# Motor_Driver_r1_1.net
KiCad netlist of a schematic drawn in Altium Designer
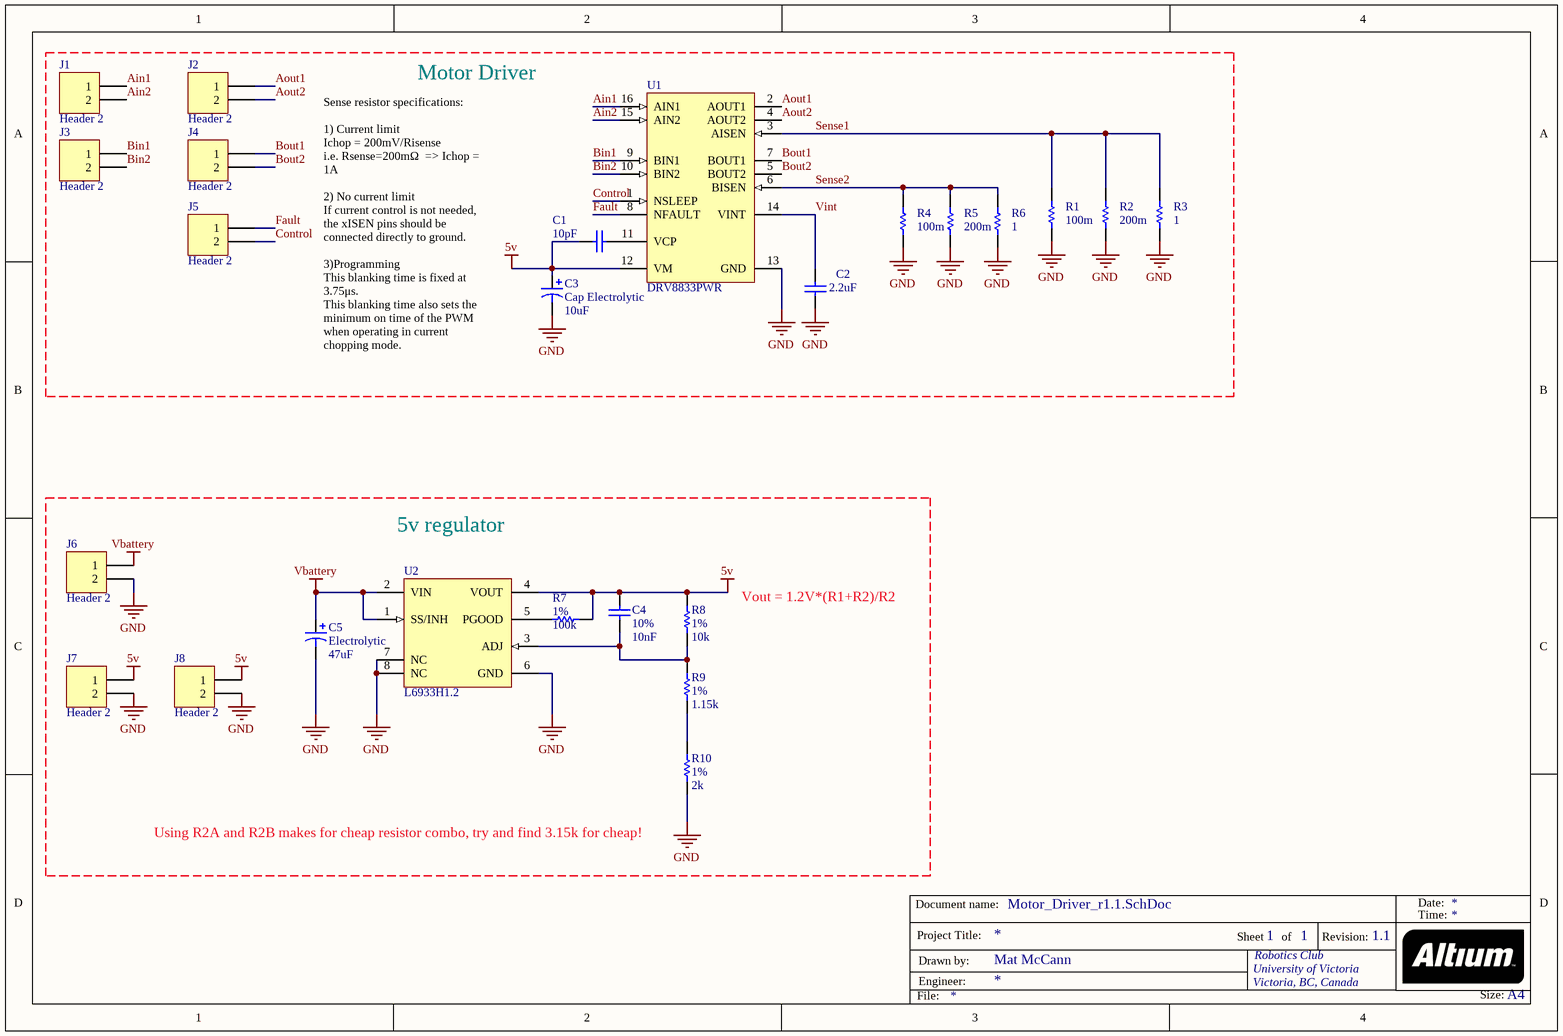
[diagram p0: Motor_Driver_r1.1.SchDoc]

(export (version "E")
  (design (tool "Eeschema 10.0.6"))
  (components
    (comp (ref "C1")
      (value "10pF")
      (footprint "6-0805_M")
      (description "Capacitor")
      (fields (field (name "Comment") "cap") (field (name "PUBLISHER") "Altium Limited"))
      (libsource (lib "Miscellaneous Devices") (part "Cap"))
    )
    (comp (ref "C2")
      (value "2.2uF")
      (footprint "6-0805_M")
      (description "Capacitor")
      (fields (field (name "Comment") "cap") (field (name "PUBLISHER") "Altium Limited"))
      (libsource (lib "Miscellaneous Devices") (part "Cap"))
    )
    (comp (ref "C3")
      (value "Cap Electrolytic")
      (footprint "capacitor_3d")
      (description "Polarized Capacitor (Radial)")
      (fields (field (name "ALTIUM_VALUE") "10uF") (field (name "PUBLISHER") "Altium Limited"))
      (libsource (lib "Miscellaneous Devices") (part "Cap Pol1"))
    )
    (comp (ref "C4")
      (value "10%")
      (footprint "6-0805_M")
      (description "Capacitor")
      (fields (field (name "ALTIUM_VALUE") "10nF") (field (name "PUBLISHER") "Altium Limited"))
      (libsource (lib "Miscellaneous Devices") (part "Cap"))
    )
    (comp (ref "C5")
      (value "Electrolytic")
      (footprint "capacitor_tantalum")
      (description "Polarized Capacitor (Radial)")
      (fields (field (name "ALTIUM_VALUE") "47uF") (field (name "PUBLISHER") "Altium Limited"))
      (libsource (lib "Miscellaneous Devices") (part "Cap Pol1"))
    )
    (comp (ref "J1")
      (value "Header 2")
      (footprint "HDR1X2")
      (description "Header, 2-Pin")
      (fields (field (name "PUBLISHER") "Altium Limited"))
      (libsource (lib "Miscellaneous Connectors") (part "Header 2"))
    )
    (comp (ref "J2")
      (value "Header 2")
      (footprint "HDR1X2")
      (description "Header, 2-Pin")
      (fields (field (name "PUBLISHER") "Altium Limited"))
      (libsource (lib "Miscellaneous Connectors") (part "Header 2"))
    )
    (comp (ref "J3")
      (value "Header 2")
      (footprint "HDR1X2")
      (description "Header, 2-Pin")
      (fields (field (name "PUBLISHER") "Altium Limited"))
      (libsource (lib "Miscellaneous Connectors") (part "Header 2"))
    )
    (comp (ref "J4")
      (value "Header 2")
      (footprint "HDR1X2")
      (description "Header, 2-Pin")
      (fields (field (name "PUBLISHER") "Altium Limited"))
      (libsource (lib "Miscellaneous Connectors") (part "Header 2"))
    )
    (comp (ref "J5")
      (value "Header 2")
      (footprint "HDR1X2")
      (description "Header, 2-Pin")
      (fields (field (name "PUBLISHER") "Altium Limited"))
      (libsource (lib "Miscellaneous Connectors") (part "Header 2"))
    )
    (comp (ref "J6")
      (value "Header 2")
      (footprint "HDR1X2")
      (description "Header, 2-Pin")
      (fields (field (name "PUBLISHER") "Altium Limited"))
      (libsource (lib "Miscellaneous Connectors") (part "Header 2"))
    )
    (comp (ref "J7")
      (value "Header 2")
      (footprint "HDR1X2")
      (description "Header, 2-Pin")
      (fields (field (name "PUBLISHER") "Altium Limited"))
      (libsource (lib "Miscellaneous Connectors") (part "Header 2"))
    )
    (comp (ref "J8")
      (value "Header 2")
      (footprint "HDR1X2")
      (description "Header, 2-Pin")
      (fields (field (name "PUBLISHER") "Altium Limited"))
      (libsource (lib "Miscellaneous Connectors") (part "Header 2"))
    )
    (comp (ref "R1")
      (value "100m")
      (footprint "6-0805_M")
      (description "Resistor")
      (fields (field (name "Comment") "Res1") (field (name "PUBLISHER") "Altium Limited"))
      (libsource (lib "Miscellaneous Devices") (part "Res1"))
    )
    (comp (ref "R2")
      (value "200m")
      (footprint "6-0805_M")
      (description "Resistor")
      (fields (field (name "Comment") "Res1") (field (name "PUBLISHER") "Altium Limited"))
      (libsource (lib "Miscellaneous Devices") (part "Res1"))
    )
    (comp (ref "R3")
      (value "1")
      (footprint "6-0805_M")
      (description "Resistor")
      (fields (field (name "Comment") "Res1") (field (name "PUBLISHER") "Altium Limited"))
      (libsource (lib "Miscellaneous Devices") (part "Res1"))
    )
    (comp (ref "R4")
      (value "100m")
      (footprint "6-0805_M")
      (description "Resistor")
      (fields (field (name "Comment") "Res1") (field (name "PUBLISHER") "Altium Limited"))
      (libsource (lib "Miscellaneous Devices") (part "Res1"))
    )
    (comp (ref "R5")
      (value "200m")
      (footprint "6-0805_M")
      (description "Resistor")
      (fields (field (name "Comment") "Res1") (field (name "PUBLISHER") "Altium Limited"))
      (libsource (lib "Miscellaneous Devices") (part "Res1"))
    )
    (comp (ref "R6")
      (value "1")
      (footprint "6-0805_M")
      (description "Resistor")
      (fields (field (name "Comment") "Res1") (field (name "PUBLISHER") "Altium Limited"))
      (libsource (lib "Miscellaneous Devices") (part "Res1"))
    )
    (comp (ref "R7")
      (value "1%")
      (footprint "6-0805_M")
      (description "Resistor")
      (fields (field (name "ALTIUM_VALUE") "100k") (field (name "PUBLISHER") "Altium Limited"))
      (libsource (lib "Miscellaneous Devices") (part "Res1"))
    )
    (comp (ref "R8")
      (value "1%")
      (footprint "6-0805_M")
      (description "Resistor")
      (fields (field (name "ALTIUM_VALUE") "10k") (field (name "PUBLISHER") "Altium Limited"))
      (libsource (lib "Miscellaneous Devices") (part "Res1"))
    )
    (comp (ref "R9")
      (value "1%")
      (footprint "6-0805_M")
      (description "Resistor")
      (fields (field (name "ALTIUM_VALUE") "1.15k") (field (name "PUBLISHER") "Altium Limited"))
      (libsource (lib "Miscellaneous Devices") (part "Res1"))
    )
    (comp (ref "R10")
      (value "1%")
      (footprint "6-0805_M")
      (description "Resistor")
      (fields (field (name "ALTIUM_VALUE") "2k") (field (name "PUBLISHER") "Altium Limited"))
      (libsource (lib "Miscellaneous Devices") (part "Res1"))
    )
    (comp (ref "U1")
      (value "DRV8833PWR")
      (footprint "TI-PW16_M")
      (fields (field (name "MANUFACTURER") "Texas Instruments"))
      (libsource (lib "Altium Content Vault") (part "CMP-1529-00001-1"))
    )
    (comp (ref "U2")
      (value "L6933H1.2")
      (footprint "SO8_M")
      (description "High Performance 2A ULDO Linear Regulator with Soft Start, 8-Pin SO")
      (libsource (lib "Altium Content Vault") (part "CMP-0240-00057-1"))
    )
  )
  (nets
    (net (code "1") (name "/Ain1") (class "Default")
      (node (ref "J1") (pin "1") (pinfunction "1_1") (pintype "passive"))
      (node (ref "U1") (pin "16") (pinfunction "AIN1_16") (pintype "input"))
    )
    (net (code "2") (name "/Ain2") (class "Default")
      (node (ref "J1") (pin "2") (pinfunction "2_2") (pintype "passive"))
      (node (ref "U1") (pin "15") (pinfunction "AIN2_15") (pintype "input"))
    )
    (net (code "3") (name "/Aout1") (class "Default")
      (node (ref "J2") (pin "1") (pinfunction "1_1") (pintype "passive"))
      (node (ref "U1") (pin "2") (pinfunction "AOUT1_2") (pintype "tri_state"))
    )
    (net (code "4") (name "/Aout2") (class "Default")
      (node (ref "J2") (pin "2") (pinfunction "2_2") (pintype "passive"))
      (node (ref "U1") (pin "4") (pinfunction "AOUT2_4") (pintype "tri_state"))
    )
    (net (code "5") (name "/Bin1") (class "Default")
      (node (ref "J3") (pin "1") (pinfunction "1_1") (pintype "passive"))
      (node (ref "U1") (pin "9") (pinfunction "BIN1_9") (pintype "input"))
    )
    (net (code "6") (name "/Bin2") (class "Default")
      (node (ref "J3") (pin "2") (pinfunction "2_2") (pintype "passive"))
      (node (ref "U1") (pin "10") (pinfunction "BIN2_10") (pintype "input"))
    )
    (net (code "7") (name "/Bout1") (class "Default")
      (node (ref "J4") (pin "1") (pinfunction "1_1") (pintype "passive"))
      (node (ref "U1") (pin "7") (pinfunction "BOUT1_7") (pintype "tri_state"))
    )
    (net (code "8") (name "/Bout2") (class "Default")
      (node (ref "J4") (pin "2") (pinfunction "2_2") (pintype "passive"))
      (node (ref "U1") (pin "5") (pinfunction "BOUT2_5") (pintype "tri_state"))
    )
    (net (code "9") (name "/Control") (class "Default")
      (node (ref "J5") (pin "2") (pinfunction "2_2") (pintype "passive"))
      (node (ref "U1") (pin "1") (pinfunction "NSLEEP_1") (pintype "input"))
    )
    (net (code "10") (name "/Fault") (class "Default")
      (node (ref "J5") (pin "1") (pinfunction "1_1") (pintype "passive"))
      (node (ref "U1") (pin "8") (pinfunction "NFAULT_8") (pintype "open_collector"))
    )
    (net (code "11") (name "/Sense1") (class "Default")
      (node (ref "R1") (pin "2") (pinfunction "2_2") (pintype "passive"))
      (node (ref "R2") (pin "2") (pinfunction "2_2") (pintype "passive"))
      (node (ref "R3") (pin "2") (pinfunction "2_2") (pintype "passive"))
      (node (ref "U1") (pin "3") (pinfunction "AISEN_3") (pintype "input"))
    )
    (net (code "12") (name "/Sense2") (class "Default")
      (node (ref "R4") (pin "2") (pinfunction "2_2") (pintype "passive"))
      (node (ref "R5") (pin "2") (pinfunction "2_2") (pintype "passive"))
      (node (ref "R6") (pin "2") (pinfunction "2_2") (pintype "passive"))
      (node (ref "U1") (pin "6") (pinfunction "BISEN_6") (pintype "input"))
    )
    (net (code "13") (name "/Vint") (class "Default")
      (node (ref "C2") (pin "2") (pinfunction "2_2") (pintype "passive"))
      (node (ref "U1") (pin "14") (pinfunction "VINT_14") (pintype "passive"))
    )
    (net (code "14") (name "5v") (class "Default")
      (node (ref "C1") (pin "2") (pinfunction "2_2") (pintype "passive"))
      (node (ref "C3") (pin "1") (pinfunction "1_1") (pintype "passive"))
      (node (ref "C4") (pin "2") (pinfunction "2_2") (pintype "passive"))
      (node (ref "J7") (pin "1") (pinfunction "1_1") (pintype "passive"))
      (node (ref "J8") (pin "1") (pinfunction "1_1") (pintype "passive"))
      (node (ref "R7") (pin "2") (pinfunction "2_2") (pintype "passive"))
      (node (ref "R8") (pin "2") (pinfunction "2_2") (pintype "passive"))
      (node (ref "U1") (pin "12") (pinfunction "VM_12") (pintype "power_in"))
      (node (ref "U2") (pin "4") (pinfunction "VOUT_4") (pintype "power_in"))
    )
    (net (code "15") (name "GND") (class "Default")
      (node (ref "C2") (pin "1") (pinfunction "1_1") (pintype "passive"))
      (node (ref "C3") (pin "2") (pinfunction "2_2") (pintype "passive"))
      (node (ref "C5") (pin "2") (pinfunction "2_2") (pintype "passive"))
      (node (ref "J6") (pin "2") (pinfunction "2_2") (pintype "passive"))
      (node (ref "J7") (pin "2") (pinfunction "2_2") (pintype "passive"))
      (node (ref "J8") (pin "2") (pinfunction "2_2") (pintype "passive"))
      (node (ref "R1") (pin "1") (pinfunction "1_1") (pintype "passive"))
      (node (ref "R10") (pin "1") (pinfunction "1_1") (pintype "passive"))
      (node (ref "R2") (pin "1") (pinfunction "1_1") (pintype "passive"))
      (node (ref "R3") (pin "1") (pinfunction "1_1") (pintype "passive"))
      (node (ref "R4") (pin "1") (pinfunction "1_1") (pintype "passive"))
      (node (ref "R5") (pin "1") (pinfunction "1_1") (pintype "passive"))
      (node (ref "R6") (pin "1") (pinfunction "1_1") (pintype "passive"))
      (node (ref "U1") (pin "13") (pinfunction "GND_13") (pintype "power_in"))
      (node (ref "U2") (pin "6") (pinfunction "GND_6") (pintype "power_in"))
      (node (ref "U2") (pin "7") (pinfunction "NC_7") (pintype "passive"))
      (node (ref "U2") (pin "8") (pinfunction "NC_8") (pintype "passive"))
    )
    (net (code "16") (name "Net-(R10-Pad2)") (class "Default")
      (node (ref "R10") (pin "2") (pinfunction "2_2") (pintype "passive"))
      (node (ref "R9") (pin "1") (pinfunction "1_1") (pintype "passive"))
    )
    (net (code "17") (name "Net-(U1-VCP)") (class "Default")
      (node (ref "C1") (pin "1") (pinfunction "1_1") (pintype "passive"))
      (node (ref "U1") (pin "11") (pinfunction "VCP_11") (pintype "passive"))
    )
    (net (code "18") (name "Net-(U2-ADJ)") (class "Default")
      (node (ref "C4") (pin "1") (pinfunction "1_1") (pintype "passive"))
      (node (ref "R8") (pin "1") (pinfunction "1_1") (pintype "passive"))
      (node (ref "R9") (pin "2") (pinfunction "2_2") (pintype "passive"))
      (node (ref "U2") (pin "3") (pinfunction "ADJ_3") (pintype "input"))
    )
    (net (code "19") (name "Net-(U2-PGOOD)") (class "Default")
      (node (ref "R7") (pin "1") (pinfunction "1_1") (pintype "passive"))
      (node (ref "U2") (pin "5") (pinfunction "PGOOD_5") (pintype "open_collector"))
    )
    (net (code "20") (name "Vbattery") (class "Default")
      (node (ref "C5") (pin "1") (pinfunction "1_1") (pintype "passive"))
      (node (ref "J6") (pin "1") (pinfunction "1_1") (pintype "passive"))
      (node (ref "U2") (pin "1") (pinfunction "SS/INH_1") (pintype "input"))
      (node (ref "U2") (pin "2") (pinfunction "VIN_2") (pintype "power_in"))
    )
  )
)
